# Sheet1_GMAX0505_2518_MB.net
KiCad netlist of a schematic drawn in Altium Designer
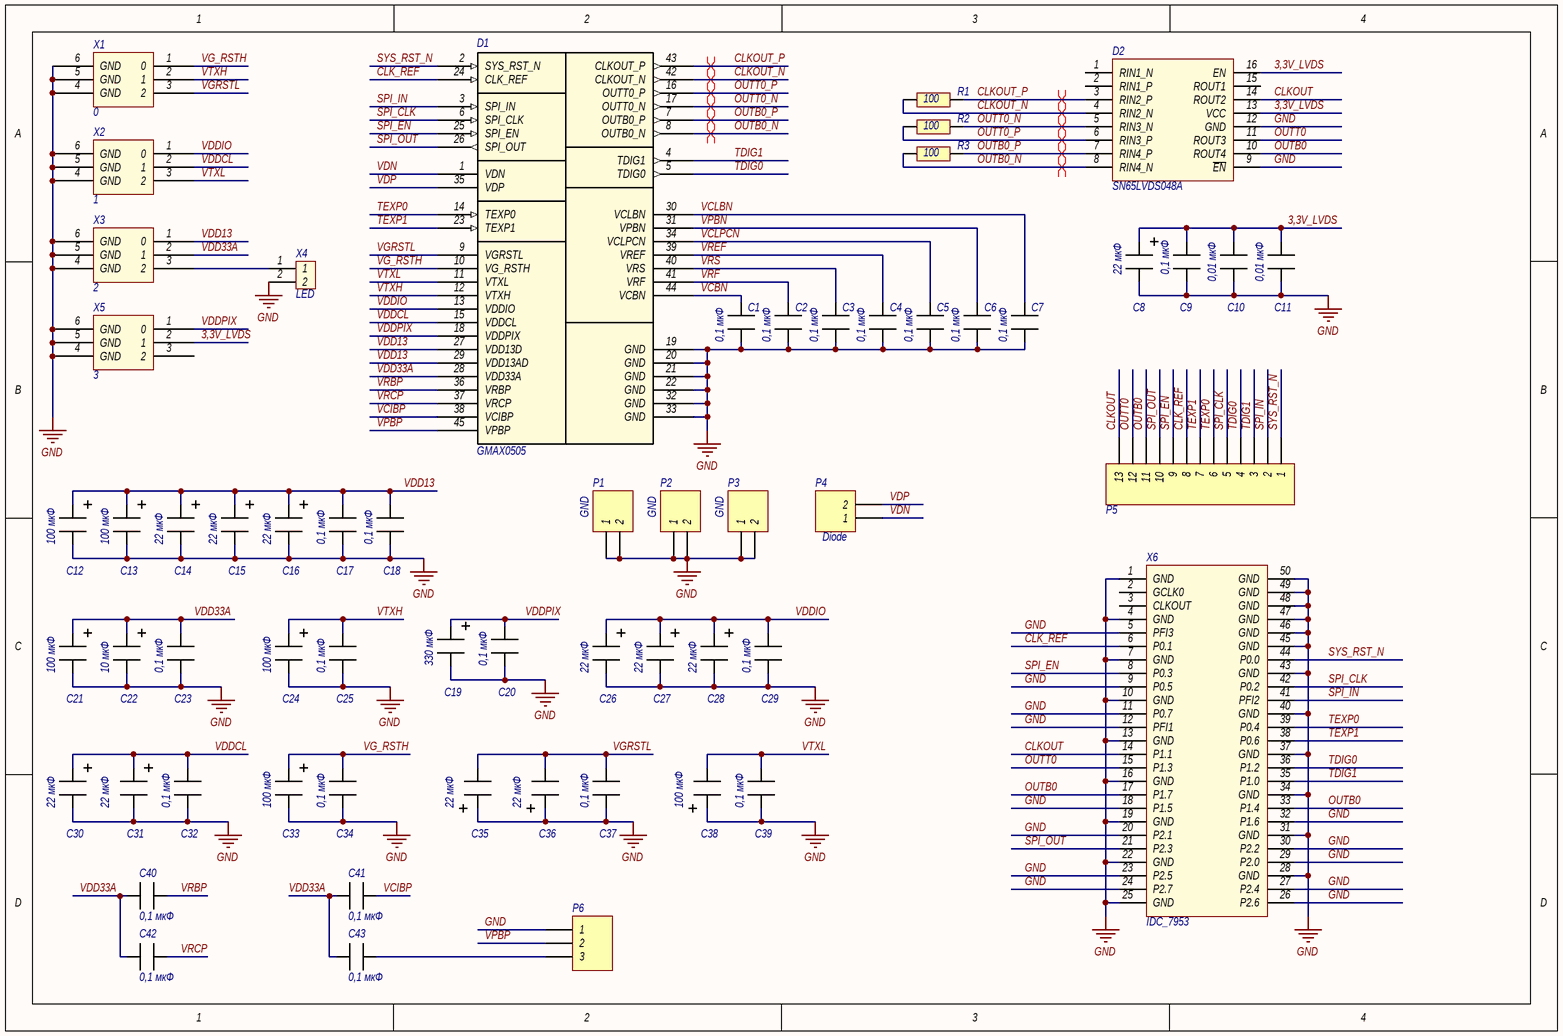
[diagram p0: Sheet1_GMAX0505_2518_MB.SchDoc]

(export (version "E")
  (design (tool "Eeschema 10.0.6"))
  (components
    (comp (ref "C1") (value "0,1 мкФ") (footprint "CAP_SMALL") (libsource (lib "Schlib") (part "CAP_SMALL")))
    (comp (ref "C2") (value "0,1 мкФ") (footprint "CAP_SMALL") (libsource (lib "Schlib") (part "CAP_SMALL")))
    (comp (ref "C3") (value "0,1 мкФ") (footprint "CAP_SMALL") (libsource (lib "Schlib") (part "CAP_SMALL")))
    (comp (ref "C4") (value "0,1 мкФ") (footprint "CAP_SMALL") (libsource (lib "Schlib") (part "CAP_SMALL")))
    (comp (ref "C5") (value "0,1 мкФ") (footprint "CAP_SMALL") (libsource (lib "Schlib") (part "CAP_SMALL")))
    (comp (ref "C6") (value "0,1 мкФ") (footprint "CAP_SMALL") (libsource (lib "Schlib") (part "CAP_SMALL")))
    (comp (ref "C7") (value "0,1 мкФ") (footprint "CAP_SMALL") (libsource (lib "Schlib") (part "CAP_SMALL")))
    (comp (ref "C8")
      (value "22 мкФ")
      (footprint "Cap_0511_electrolitic")
      (libsource (lib "Schlib") (part "Cap_electrolotoc_0511"))
    )
    (comp (ref "C9") (value "0,1 мкФ") (footprint "CAP_SMALL") (libsource (lib "Schlib") (part "CAP_SMALL")))
    (comp (ref "C10")
      (value "0,01 мкФ")
      (footprint "CAP_SMALL")
      (libsource (lib "Schlib") (part "CAP_SMALL"))
    )
    (comp (ref "C11")
      (value "0,01 мкФ")
      (footprint "CAP_SMALL")
      (libsource (lib "Schlib") (part "CAP_SMALL"))
    )
    (comp (ref "C12")
      (value "100 мкФ")
      (footprint "Cap_0612_electrolitic")
      (libsource (lib "Schlib") (part "Cap_electrolotoc_0612"))
    )
    (comp (ref "C13")
      (value "100 мкФ")
      (footprint "Cap_0612_electrolitic")
      (libsource (lib "Schlib") (part "Cap_electrolotoc_0612"))
    )
    (comp (ref "C14")
      (value "22 мкФ")
      (footprint "Cap_0511_electrolitic")
      (libsource (lib "Schlib") (part "Cap_electrolotoc_0511"))
    )
    (comp (ref "C15")
      (value "22 мкФ")
      (footprint "Cap_0511_electrolitic")
      (libsource (lib "Schlib") (part "Cap_electrolotoc_0511"))
    )
    (comp (ref "C16")
      (value "22 мкФ")
      (footprint "Cap_0511_electrolitic")
      (libsource (lib "Schlib") (part "Cap_electrolotoc_0511"))
    )
    (comp (ref "C17") (value "0,1 мкФ") (footprint "CAP_SMALL") (libsource (lib "Schlib") (part "CAP_SMALL")))
    (comp (ref "C18") (value "0,1 мкФ") (footprint "CAP_SMALL") (libsource (lib "Schlib") (part "CAP_SMALL")))
    (comp (ref "C19")
      (value "330 мкФ")
      (footprint "Cap_1013_electrolitic")
      (libsource (lib "Schlib") (part "Cap_electrolotoc_1013"))
    )
    (comp (ref "C20") (value "0,1 мкФ") (footprint "CAP_SMALL") (libsource (lib "Schlib") (part "CAP_SMALL")))
    (comp (ref "C21")
      (value "100 мкФ")
      (footprint "Cap_0612_electrolitic")
      (libsource (lib "Schlib") (part "Cap_electrolotoc_0612"))
    )
    (comp (ref "C22")
      (value "10 мкФ")
      (footprint "Cap_0511_electrolitic")
      (libsource (lib "Schlib") (part "Cap_electrolotoc_0511"))
    )
    (comp (ref "C23") (value "0,1 мкФ") (footprint "CAP_SMALL") (libsource (lib "Schlib") (part "CAP_SMALL")))
    (comp (ref "C24")
      (value "100 мкФ")
      (footprint "Cap_0612_electrolitic")
      (libsource (lib "Schlib") (part "Cap_electrolotoc_0612"))
    )
    (comp (ref "C25") (value "0,1 мкФ") (footprint "CAP_SMALL") (libsource (lib "Schlib") (part "CAP_SMALL")))
    (comp (ref "C26")
      (value "22 мкФ")
      (footprint "Cap_0511_electrolitic")
      (libsource (lib "Schlib") (part "Cap_electrolotoc_0511"))
    )
    (comp (ref "C27")
      (value "22 мкФ")
      (footprint "Cap_0511_electrolitic")
      (libsource (lib "Schlib") (part "Cap_electrolotoc_0511"))
    )
    (comp (ref "C28")
      (value "22 мкФ")
      (footprint "Cap_0511_electrolitic")
      (libsource (lib "Schlib") (part "Cap_electrolotoc_0511"))
    )
    (comp (ref "C29") (value "0,1 мкФ") (footprint "CAP_SMALL") (libsource (lib "Schlib") (part "CAP_SMALL")))
    (comp (ref "C30")
      (value "22 мкФ")
      (footprint "Cap_0511_electrolitic")
      (libsource (lib "Schlib") (part "Cap_electrolotoc_0511"))
    )
    (comp (ref "C31")
      (value "22 мкФ")
      (footprint "Cap_0511_electrolitic")
      (libsource (lib "Schlib") (part "Cap_electrolotoc_0511"))
    )
    (comp (ref "C32") (value "0,1 мкФ") (footprint "CAP_SMALL") (libsource (lib "Schlib") (part "CAP_SMALL")))
    (comp (ref "C33")
      (value "100 мкФ")
      (footprint "Cap_0612_electrolitic")
      (libsource (lib "Schlib") (part "Cap_electrolotoc_0612"))
    )
    (comp (ref "C34") (value "0,1 мкФ") (footprint "CAP_SMALL") (libsource (lib "Schlib") (part "CAP_SMALL")))
    (comp (ref "C35")
      (value "22 мкФ")
      (footprint "Cap_0511_electrolitic")
      (libsource (lib "Schlib") (part "Cap_electrolotoc_0511"))
    )
    (comp (ref "C36")
      (value "22 мкФ")
      (footprint "Cap_0511_electrolitic")
      (libsource (lib "Schlib") (part "Cap_electrolotoc_0511"))
    )
    (comp (ref "C37") (value "0,1 мкФ") (footprint "CAP_SMALL") (libsource (lib "Schlib") (part "CAP_SMALL")))
    (comp (ref "C38")
      (value "100 мкФ")
      (footprint "Cap_0612_electrolitic")
      (libsource (lib "Schlib") (part "Cap_electrolotoc_0612"))
    )
    (comp (ref "C39") (value "0,1 мкФ") (footprint "CAP_SMALL") (libsource (lib "Schlib") (part "CAP_SMALL")))
    (comp (ref "C40") (value "0,1 мкФ") (footprint "CAP_SMALL") (libsource (lib "Schlib") (part "CAP_SMALL")))
    (comp (ref "C41") (value "0,1 мкФ") (footprint "CAP_SMALL") (libsource (lib "Schlib") (part "CAP_SMALL")))
    (comp (ref "C42") (value "0,1 мкФ") (footprint "CAP_SMALL") (libsource (lib "Schlib") (part "CAP_SMALL")))
    (comp (ref "C43") (value "0,1 мкФ") (footprint "CAP_SMALL") (libsource (lib "Schlib") (part "CAP_SMALL")))
    (comp (ref "D1")
      (value "GMAX0505")
      (footprint "GMAX0505_MEZ")
      (libsource (lib "Schlib") (part "GMAX0505_MEZ"))
    )
    (comp (ref "D2")
      (value "SN65LVDS048A")
      (footprint "SN65LVDS048A (4LVDS)")
      (libsource (lib "Schlib") (part "SN65LVDS048A (4LVDS)"))
    )
    (comp (ref "P1")
      (value "GND")
      (footprint "HDR1X2")
      (description "Header, 2-Pin")
      (fields (field (name "PUBLISHER") "Altium Limited"))
      (libsource (lib "") (part "Header 2_1"))
    )
    (comp (ref "P2")
      (value "GND")
      (footprint "HDR1X2")
      (description "Header, 2-Pin")
      (fields (field (name "PUBLISHER") "Altium Limited"))
      (libsource (lib "") (part "Header 2_1"))
    )
    (comp (ref "P3")
      (value "GND")
      (footprint "HDR1X2")
      (description "Header, 2-Pin")
      (fields (field (name "PUBLISHER") "Altium Limited"))
      (libsource (lib "") (part "Header 2_1"))
    )
    (comp (ref "P4")
      (value "Diode")
      (footprint "HDR1X2")
      (description "Header, 2-Pin")
      (fields (field (name "PUBLISHER") "Altium Limited"))
      (libsource (lib "Miscellaneous Connectors") (part "Header 2"))
    )
    (comp (ref "P5")
      (value "Header 13")
      (footprint "HDR1X13")
      (description "Header, 13-Pin")
      (fields (field (name "PUBLISHER") "Altium Limited"))
      (libsource (lib "Miscellaneous Connectors") (part "Header 13"))
    )
    (comp (ref "P6")
      (value "VPBP")
      (footprint "HDR1X3")
      (description "Header, 3-Pin")
      (fields (field (name "PUBLISHER") "Altium Limited"))
      (libsource (lib "Miscellaneous Connectors") (part "Header 3"))
    )
    (comp (ref "R1") (value "100") (footprint "RES") (libsource (lib "Schlib") (part "RES")))
    (comp (ref "R2") (value "100") (footprint "RES") (libsource (lib "Schlib") (part "RES")))
    (comp (ref "R3") (value "100") (footprint "RES") (libsource (lib "Schlib") (part "RES")))
    (comp (ref "X1") (value "0") (footprint "POWER") (libsource (lib "Schlib") (part "POWER")))
    (comp (ref "X2") (value "1") (footprint "POWER") (libsource (lib "Schlib") (part "POWER")))
    (comp (ref "X3") (value "2") (footprint "POWER") (libsource (lib "Schlib") (part "POWER")))
    (comp (ref "X4") (value "LED") (footprint "KLEMMNIK_2") (libsource (lib "Schlib") (part "KLEMMNIK_2")))
    (comp (ref "X5") (value "3") (footprint "POWER") (libsource (lib "Schlib") (part "POWER")))
    (comp (ref "X6") (value "IDC_7953") (footprint "IDC_7953") (libsource (lib "VPL") (part "IDC_7953")))
  )
  (nets
    (net (code "1") (name "/3,3V_LVDS") (class "Default")
      (node (ref "C10") (pin "2") (pinfunction "2_2") (pintype "passive"))
      (node (ref "C11") (pin "2") (pinfunction "2_2") (pintype "passive"))
      (node (ref "C8") (pin "1") (pinfunction "1_1") (pintype "passive"))
      (node (ref "C9") (pin "2") (pinfunction "2_2") (pintype "passive"))
      (node (ref "D2") (pin "13") (pinfunction "VCC_13") (pintype "passive"))
      (node (ref "D2") (pin "16") (pinfunction "EN_16") (pintype "passive"))
      (node (ref "X5") (pin "2") (pinfunction "1_2") (pintype "passive"))
    )
    (net (code "2") (name "/CLKOUT") (class "Default")
      (node (ref "D2") (pin "14") (pinfunction "ROUT2_14") (pintype "passive"))
      (node (ref "P5") (pin "13") (pinfunction "13_13") (pintype "passive"))
      (node (ref "X6") (pin "14") (pinfunction "P1.1_14") (pintype "passive"))
    )
    (net (code "3") (name "/CLKOUT_N") (class "Default")
      (node (ref "D1") (pin "42") (pinfunction "CLKOUT_N_42") (pintype "output"))
      (node (ref "D2") (pin "4") (pinfunction "RIN2_N_4") (pintype "passive"))
      (node (ref "R1") (pin "2") (pinfunction "2_2") (pintype "passive"))
    )
    (net (code "4") (name "/CLKOUT_P") (class "Default")
      (node (ref "D1") (pin "43") (pinfunction "CLKOUT_P_43") (pintype "output"))
      (node (ref "D2") (pin "3") (pinfunction "RIN2_P_3") (pintype "passive"))
      (node (ref "R1") (pin "1") (pinfunction "1_1") (pintype "passive"))
    )
    (net (code "5") (name "/CLK_REF") (class "Default")
      (node (ref "D1") (pin "24") (pinfunction "CLK_REF_24") (pintype "input"))
      (node (ref "P5") (pin "8") (pinfunction "8_8") (pintype "passive"))
      (node (ref "X6") (pin "6") (pinfunction "P0.1_6") (pintype "passive"))
    )
    (net (code "6") (name "/OUTB0") (class "Default")
      (node (ref "D2") (pin "10") (pinfunction "ROUT4_10") (pintype "passive"))
      (node (ref "P5") (pin "11") (pinfunction "11_11") (pintype "passive"))
      (node (ref "X6") (pin "17") (pinfunction "P1.7_17") (pintype "passive"))
      (node (ref "X6") (pin "33") (pinfunction "P1.4_33") (pintype "passive"))
    )
    (net (code "7") (name "/OUTB0_N") (class "Default")
      (node (ref "D1") (pin "8") (pinfunction "OUTB0_N_8") (pintype "output"))
      (node (ref "D2") (pin "8") (pinfunction "RIN4_N_8") (pintype "passive"))
      (node (ref "R3") (pin "2") (pinfunction "2_2") (pintype "passive"))
    )
    (net (code "8") (name "/OUTB0_P") (class "Default")
      (node (ref "D1") (pin "7") (pinfunction "OUTB0_P_7") (pintype "output"))
      (node (ref "D2") (pin "7") (pinfunction "RIN4_P_7") (pintype "passive"))
      (node (ref "R3") (pin "1") (pinfunction "1_1") (pintype "passive"))
    )
    (net (code "9") (name "/OUTT0") (class "Default")
      (node (ref "D2") (pin "11") (pinfunction "ROUT3_11") (pintype "passive"))
      (node (ref "P5") (pin "12") (pinfunction "12_12") (pintype "passive"))
      (node (ref "X6") (pin "15") (pinfunction "P1.3_15") (pintype "passive"))
    )
    (net (code "10") (name "/OUTT0_N") (class "Default")
      (node (ref "D1") (pin "17") (pinfunction "OUTT0_N_17") (pintype "output"))
      (node (ref "D2") (pin "5") (pinfunction "RIN3_N_5") (pintype "passive"))
      (node (ref "R2") (pin "1") (pinfunction "1_1") (pintype "passive"))
    )
    (net (code "11") (name "/OUTT0_P") (class "Default")
      (node (ref "D1") (pin "16") (pinfunction "OUTT0_P_16") (pintype "output"))
      (node (ref "D2") (pin "6") (pinfunction "RIN3_P_6") (pintype "passive"))
      (node (ref "R2") (pin "2") (pinfunction "2_2") (pintype "passive"))
    )
    (net (code "12") (name "/SPI_CLK") (class "Default")
      (node (ref "D1") (pin "6") (pinfunction "SPI_CLK_6") (pintype "input"))
      (node (ref "P5") (pin "5") (pinfunction "5_5") (pintype "passive"))
      (node (ref "X6") (pin "42") (pinfunction "P0.2_42") (pintype "passive"))
    )
    (net (code "13") (name "/SPI_EN") (class "Default")
      (node (ref "D1") (pin "25") (pinfunction "SPI_EN_25") (pintype "input"))
      (node (ref "P5") (pin "9") (pinfunction "9_9") (pintype "passive"))
      (node (ref "X6") (pin "8") (pinfunction "P0.3_8") (pintype "passive"))
    )
    (net (code "14") (name "/SPI_IN") (class "Default")
      (node (ref "D1") (pin "3") (pinfunction "SPI_IN_3") (pintype "input"))
      (node (ref "P5") (pin "2") (pinfunction "2_2") (pintype "passive"))
      (node (ref "X6") (pin "41") (pinfunction "PFI2_41") (pintype "passive"))
    )
    (net (code "15") (name "/SPI_OUT") (class "Default")
      (node (ref "D1") (pin "26") (pinfunction "SPI_OUT_26") (pintype "output"))
      (node (ref "P5") (pin "10") (pinfunction "10_10") (pintype "passive"))
      (node (ref "X6") (pin "21") (pinfunction "P2.3_21") (pintype "passive"))
    )
    (net (code "16") (name "/SYS_RST_N") (class "Default")
      (node (ref "D1") (pin "2") (pinfunction "SYS_RST_N_2") (pintype "input"))
      (node (ref "P5") (pin "1") (pinfunction "1_1") (pintype "passive"))
      (node (ref "X6") (pin "44") (pinfunction "P0.0_44") (pintype "passive"))
    )
    (net (code "17") (name "/TDIG0") (class "Default")
      (node (ref "D1") (pin "5") (pinfunction "TDIG0_5") (pintype "output"))
      (node (ref "P5") (pin "4") (pinfunction "4_4") (pintype "passive"))
      (node (ref "X6") (pin "36") (pinfunction "P1.2_36") (pintype "passive"))
    )
    (net (code "18") (name "/TDIG1") (class "Default")
      (node (ref "D1") (pin "4") (pinfunction "TDIG1_4") (pintype "output"))
      (node (ref "P5") (pin "3") (pinfunction "3_3") (pintype "passive"))
      (node (ref "X6") (pin "35") (pinfunction "P1.0_35") (pintype "passive"))
    )
    (net (code "19") (name "/TEXP0") (class "Default")
      (node (ref "D1") (pin "14") (pinfunction "TEXP0_14") (pintype "input"))
      (node (ref "P5") (pin "6") (pinfunction "6_6") (pintype "passive"))
      (node (ref "X6") (pin "39") (pinfunction "P0.4_39") (pintype "passive"))
    )
    (net (code "20") (name "/TEXP1") (class "Default")
      (node (ref "D1") (pin "23") (pinfunction "TEXP1_23") (pintype "input"))
      (node (ref "P5") (pin "7") (pinfunction "7_7") (pintype "passive"))
      (node (ref "X6") (pin "38") (pinfunction "P0.6_38") (pintype "passive"))
    )
    (net (code "21") (name "/VCBN") (class "Default")
      (node (ref "C1") (pin "1") (pinfunction "1_1") (pintype "passive"))
      (node (ref "D1") (pin "44") (pinfunction "VCBN_44") (pintype "passive"))
    )
    (net (code "22") (name "/VCIBP") (class "Default")
      (node (ref "C41") (pin "1") (pinfunction "1_1") (pintype "passive"))
      (node (ref "D1") (pin "38") (pinfunction "VCIBP_38") (pintype "passive"))
    )
    (net (code "23") (name "/VCLBN") (class "Default")
      (node (ref "C7") (pin "1") (pinfunction "1_1") (pintype "passive"))
      (node (ref "D1") (pin "30") (pinfunction "VCLBN_30") (pintype "passive"))
    )
    (net (code "24") (name "/VCLPCN") (class "Default")
      (node (ref "C5") (pin "1") (pinfunction "1_1") (pintype "passive"))
      (node (ref "D1") (pin "34") (pinfunction "VCLPCN_34") (pintype "passive"))
    )
    (net (code "25") (name "/VDD13") (class "Default")
      (node (ref "C12") (pin "1") (pinfunction "1_1") (pintype "passive"))
      (node (ref "C13") (pin "1") (pinfunction "1_1") (pintype "passive"))
      (node (ref "C14") (pin "1") (pinfunction "1_1") (pintype "passive"))
      (node (ref "C15") (pin "1") (pinfunction "1_1") (pintype "passive"))
      (node (ref "C16") (pin "1") (pinfunction "1_1") (pintype "passive"))
      (node (ref "C17") (pin "1") (pinfunction "1_1") (pintype "passive"))
      (node (ref "C18") (pin "1") (pinfunction "1_1") (pintype "passive"))
      (node (ref "D1") (pin "27") (pinfunction "VDD13D_27") (pintype "passive"))
      (node (ref "D1") (pin "29") (pinfunction "VDD13AD_29") (pintype "passive"))
      (node (ref "X3") (pin "1") (pinfunction "0_1") (pintype "passive"))
    )
    (net (code "26") (name "/VDD33A") (class "Default")
      (node (ref "C21") (pin "1") (pinfunction "1_1") (pintype "passive"))
      (node (ref "C22") (pin "1") (pinfunction "1_1") (pintype "passive"))
      (node (ref "C23") (pin "1") (pinfunction "1_1") (pintype "passive"))
      (node (ref "C40") (pin "2") (pinfunction "2_2") (pintype "passive"))
      (node (ref "C41") (pin "2") (pinfunction "2_2") (pintype "passive"))
      (node (ref "C42") (pin "2") (pinfunction "2_2") (pintype "passive"))
      (node (ref "C43") (pin "2") (pinfunction "2_2") (pintype "passive"))
      (node (ref "D1") (pin "28") (pinfunction "VDD33A_28") (pintype "passive"))
      (node (ref "X3") (pin "2") (pinfunction "1_2") (pintype "passive"))
    )
    (net (code "27") (name "/VDDCL") (class "Default")
      (node (ref "C30") (pin "1") (pinfunction "1_1") (pintype "passive"))
      (node (ref "C31") (pin "1") (pinfunction "1_1") (pintype "passive"))
      (node (ref "C32") (pin "2") (pinfunction "2_2") (pintype "passive"))
      (node (ref "D1") (pin "15") (pinfunction "VDDCL_15") (pintype "passive"))
      (node (ref "X2") (pin "2") (pinfunction "1_2") (pintype "passive"))
    )
    (net (code "28") (name "/VDDIO") (class "Default")
      (node (ref "C26") (pin "1") (pinfunction "1_1") (pintype "passive"))
      (node (ref "C27") (pin "1") (pinfunction "1_1") (pintype "passive"))
      (node (ref "C28") (pin "1") (pinfunction "1_1") (pintype "passive"))
      (node (ref "C29") (pin "1") (pinfunction "1_1") (pintype "passive"))
      (node (ref "D1") (pin "13") (pinfunction "VDDIO_13") (pintype "passive"))
      (node (ref "X2") (pin "1") (pinfunction "0_1") (pintype "passive"))
    )
    (net (code "29") (name "/VDDPIX") (class "Default")
      (node (ref "C19") (pin "1") (pinfunction "1_1") (pintype "passive"))
      (node (ref "C20") (pin "1") (pinfunction "1_1") (pintype "passive"))
      (node (ref "D1") (pin "18") (pinfunction "VDDPIX_18") (pintype "passive"))
      (node (ref "X5") (pin "1") (pinfunction "0_1") (pintype "passive"))
    )
    (net (code "30") (name "/VDN") (class "Default")
      (node (ref "D1") (pin "1") (pinfunction "VDN_1") (pintype "passive"))
      (node (ref "P4") (pin "1") (pinfunction "1_1") (pintype "passive"))
    )
    (net (code "31") (name "/VDP") (class "Default")
      (node (ref "D1") (pin "35") (pinfunction "VDP_35") (pintype "passive"))
      (node (ref "P4") (pin "2") (pinfunction "2_2") (pintype "passive"))
    )
    (net (code "32") (name "/VGRSTL") (class "Default")
      (node (ref "C35") (pin "2") (pinfunction "2_2") (pintype "passive"))
      (node (ref "C36") (pin "2") (pinfunction "2_2") (pintype "passive"))
      (node (ref "C37") (pin "2") (pinfunction "2_2") (pintype "passive"))
      (node (ref "D1") (pin "9") (pinfunction "VGRSTL_9") (pintype "passive"))
      (node (ref "X1") (pin "3") (pinfunction "2_3") (pintype "passive"))
    )
    (net (code "33") (name "/VG_RSTH") (class "Default")
      (node (ref "C33") (pin "1") (pinfunction "1_1") (pintype "passive"))
      (node (ref "C34") (pin "1") (pinfunction "1_1") (pintype "passive"))
      (node (ref "D1") (pin "10") (pinfunction "VG_RSTH_10") (pintype "passive"))
      (node (ref "X1") (pin "1") (pinfunction "0_1") (pintype "passive"))
    )
    (net (code "34") (name "/VPBN") (class "Default")
      (node (ref "C6") (pin "1") (pinfunction "1_1") (pintype "passive"))
      (node (ref "D1") (pin "31") (pinfunction "VPBN_31") (pintype "passive"))
    )
    (net (code "35") (name "/VPBP") (class "Default")
      (node (ref "D1") (pin "45") (pinfunction "VPBP_45") (pintype "passive"))
      (node (ref "P6") (pin "2") (pinfunction "2_2") (pintype "passive"))
    )
    (net (code "36") (name "/VRBP") (class "Default")
      (node (ref "C40") (pin "1") (pinfunction "1_1") (pintype "passive"))
      (node (ref "D1") (pin "36") (pinfunction "VRBP_36") (pintype "passive"))
    )
    (net (code "37") (name "/VRCP") (class "Default")
      (node (ref "C42") (pin "1") (pinfunction "1_1") (pintype "passive"))
      (node (ref "D1") (pin "37") (pinfunction "VRCP_37") (pintype "passive"))
    )
    (net (code "38") (name "/VREF") (class "Default")
      (node (ref "C4") (pin "1") (pinfunction "1_1") (pintype "passive"))
      (node (ref "D1") (pin "39") (pinfunction "VREF_39") (pintype "passive"))
    )
    (net (code "39") (name "/VRF") (class "Default")
      (node (ref "C2") (pin "1") (pinfunction "1_1") (pintype "passive"))
      (node (ref "D1") (pin "41") (pinfunction "VRF_41") (pintype "passive"))
    )
    (net (code "40") (name "/VRS") (class "Default")
      (node (ref "C3") (pin "1") (pinfunction "1_1") (pintype "passive"))
      (node (ref "D1") (pin "40") (pinfunction "VRS_40") (pintype "passive"))
    )
    (net (code "41") (name "/VTXH") (class "Default")
      (node (ref "C24") (pin "1") (pinfunction "1_1") (pintype "passive"))
      (node (ref "C25") (pin "1") (pinfunction "1_1") (pintype "passive"))
      (node (ref "D1") (pin "12") (pinfunction "VTXH_12") (pintype "passive"))
      (node (ref "X1") (pin "2") (pinfunction "1_2") (pintype "passive"))
    )
    (net (code "42") (name "/VTXL") (class "Default")
      (node (ref "C38") (pin "2") (pinfunction "2_2") (pintype "passive"))
      (node (ref "C39") (pin "1") (pinfunction "1_1") (pintype "passive"))
      (node (ref "D1") (pin "11") (pinfunction "VTXL_11") (pintype "passive"))
      (node (ref "X2") (pin "3") (pinfunction "2_3") (pintype "passive"))
    )
    (net (code "43") (name "GND") (class "Default")
      (node (ref "C1") (pin "2") (pinfunction "2_2") (pintype "passive"))
      (node (ref "C10") (pin "1") (pinfunction "1_1") (pintype "passive"))
      (node (ref "C11") (pin "1") (pinfunction "1_1") (pintype "passive"))
      (node (ref "C12") (pin "2") (pinfunction "2_2") (pintype "passive"))
      (node (ref "C13") (pin "2") (pinfunction "2_2") (pintype "passive"))
      (node (ref "C14") (pin "2") (pinfunction "2_2") (pintype "passive"))
      (node (ref "C15") (pin "2") (pinfunction "2_2") (pintype "passive"))
      (node (ref "C16") (pin "2") (pinfunction "2_2") (pintype "passive"))
      (node (ref "C17") (pin "2") (pinfunction "2_2") (pintype "passive"))
      (node (ref "C18") (pin "2") (pinfunction "2_2") (pintype "passive"))
      (node (ref "C19") (pin "2") (pinfunction "2_2") (pintype "passive"))
      (node (ref "C2") (pin "2") (pinfunction "2_2") (pintype "passive"))
      (node (ref "C20") (pin "2") (pinfunction "2_2") (pintype "passive"))
      (node (ref "C21") (pin "2") (pinfunction "2_2") (pintype "passive"))
      (node (ref "C22") (pin "2") (pinfunction "2_2") (pintype "passive"))
      (node (ref "C23") (pin "2") (pinfunction "2_2") (pintype "passive"))
      (node (ref "C24") (pin "2") (pinfunction "2_2") (pintype "passive"))
      (node (ref "C25") (pin "2") (pinfunction "2_2") (pintype "passive"))
      (node (ref "C26") (pin "2") (pinfunction "2_2") (pintype "passive"))
      (node (ref "C27") (pin "2") (pinfunction "2_2") (pintype "passive"))
      (node (ref "C28") (pin "2") (pinfunction "2_2") (pintype "passive"))
      (node (ref "C29") (pin "2") (pinfunction "2_2") (pintype "passive"))
      (node (ref "C3") (pin "2") (pinfunction "2_2") (pintype "passive"))
      (node (ref "C30") (pin "2") (pinfunction "2_2") (pintype "passive"))
      (node (ref "C31") (pin "2") (pinfunction "2_2") (pintype "passive"))
      (node (ref "C32") (pin "1") (pinfunction "1_1") (pintype "passive"))
      (node (ref "C33") (pin "2") (pinfunction "2_2") (pintype "passive"))
      (node (ref "C34") (pin "2") (pinfunction "2_2") (pintype "passive"))
      (node (ref "C35") (pin "1") (pinfunction "1_1") (pintype "passive"))
      (node (ref "C36") (pin "1") (pinfunction "1_1") (pintype "passive"))
      (node (ref "C37") (pin "1") (pinfunction "1_1") (pintype "passive"))
      (node (ref "C38") (pin "1") (pinfunction "1_1") (pintype "passive"))
      (node (ref "C39") (pin "2") (pinfunction "2_2") (pintype "passive"))
      (node (ref "C4") (pin "2") (pinfunction "2_2") (pintype "passive"))
      (node (ref "C5") (pin "2") (pinfunction "2_2") (pintype "passive"))
      (node (ref "C6") (pin "2") (pinfunction "2_2") (pintype "passive"))
      (node (ref "C7") (pin "2") (pinfunction "2_2") (pintype "passive"))
      (node (ref "C8") (pin "2") (pinfunction "2_2") (pintype "passive"))
      (node (ref "C9") (pin "1") (pinfunction "1_1") (pintype "passive"))
      (node (ref "D1") (pin "19") (pinfunction "GND_19") (pintype "passive"))
      (node (ref "D1") (pin "20") (pinfunction "GND_20") (pintype "passive"))
      (node (ref "D1") (pin "21") (pinfunction "GND_21") (pintype "passive"))
      (node (ref "D1") (pin "22") (pinfunction "GND_22") (pintype "passive"))
      (node (ref "D1") (pin "32") (pinfunction "GND_32") (pintype "passive"))
      (node (ref "D1") (pin "33") (pinfunction "GND_33") (pintype "passive"))
      (node (ref "D2") (pin "12") (pinfunction "GND_12") (pintype "passive"))
      (node (ref "D2") (pin "9") (pinfunction "~{EN}_9") (pintype "passive"))
      (node (ref "P1") (pin "1") (pinfunction "1_1") (pintype "passive"))
      (node (ref "P1") (pin "2") (pinfunction "2_2") (pintype "passive"))
      (node (ref "P2") (pin "1") (pinfunction "1_1") (pintype "passive"))
      (node (ref "P2") (pin "2") (pinfunction "2_2") (pintype "passive"))
      (node (ref "P3") (pin "1") (pinfunction "1_1") (pintype "passive"))
      (node (ref "P3") (pin "2") (pinfunction "2_2") (pintype "passive"))
      (node (ref "P6") (pin "1") (pinfunction "1_1") (pintype "passive"))
      (node (ref "X1") (pin "4") (pinfunction "GND_4") (pintype "passive"))
      (node (ref "X1") (pin "5") (pinfunction "GND_5") (pintype "passive"))
      (node (ref "X1") (pin "6") (pinfunction "GND_6") (pintype "passive"))
      (node (ref "X2") (pin "4") (pinfunction "GND_4") (pintype "passive"))
      (node (ref "X2") (pin "5") (pinfunction "GND_5") (pintype "passive"))
      (node (ref "X2") (pin "6") (pinfunction "GND_6") (pintype "passive"))
      (node (ref "X3") (pin "4") (pinfunction "GND_4") (pintype "passive"))
      (node (ref "X3") (pin "5") (pinfunction "GND_5") (pintype "passive"))
      (node (ref "X3") (pin "6") (pinfunction "GND_6") (pintype "passive"))
      (node (ref "X4") (pin "2") (pinfunction "2_2") (pintype "passive"))
      (node (ref "X5") (pin "4") (pinfunction "GND_4") (pintype "passive"))
      (node (ref "X5") (pin "5") (pinfunction "GND_5") (pintype "passive"))
      (node (ref "X5") (pin "6") (pinfunction "GND_6") (pintype "passive"))
      (node (ref "X6") (pin "1") (pinfunction "GND_1") (pintype "passive"))
      (node (ref "X6") (pin "10") (pinfunction "GND_10") (pintype "passive"))
      (node (ref "X6") (pin "11") (pinfunction "P0.7_11") (pintype "passive"))
      (node (ref "X6") (pin "12") (pinfunction "PFI1_12") (pintype "passive"))
      (node (ref "X6") (pin "13") (pinfunction "GND_13") (pintype "passive"))
      (node (ref "X6") (pin "16") (pinfunction "GND_16") (pintype "passive"))
      (node (ref "X6") (pin "18") (pinfunction "P1.5_18") (pintype "passive"))
      (node (ref "X6") (pin "19") (pinfunction "GND_19") (pintype "passive"))
      (node (ref "X6") (pin "20") (pinfunction "P2.1_20") (pintype "passive"))
      (node (ref "X6") (pin "22") (pinfunction "GND_22") (pintype "passive"))
      (node (ref "X6") (pin "23") (pinfunction "P2.5_23") (pintype "passive"))
      (node (ref "X6") (pin "24") (pinfunction "P2.7_24") (pintype "passive"))
      (node (ref "X6") (pin "25") (pinfunction "GND_25") (pintype "passive"))
      (node (ref "X6") (pin "26") (pinfunction "P2.6_26") (pintype "passive"))
      (node (ref "X6") (pin "27") (pinfunction "P2.4_27") (pintype "passive"))
      (node (ref "X6") (pin "28") (pinfunction "GND_28") (pintype "passive"))
      (node (ref "X6") (pin "29") (pinfunction "P2.0_29") (pintype "passive"))
      (node (ref "X6") (pin "30") (pinfunction "P2.2_30") (pintype "passive"))
      (node (ref "X6") (pin "31") (pinfunction "GND_31") (pintype "passive"))
      (node (ref "X6") (pin "32") (pinfunction "P1.6_32") (pintype "passive"))
      (node (ref "X6") (pin "34") (pinfunction "GND_34") (pintype "passive"))
      (node (ref "X6") (pin "37") (pinfunction "GND_37") (pintype "passive"))
      (node (ref "X6") (pin "4") (pinfunction "GND_4") (pintype "passive"))
      (node (ref "X6") (pin "40") (pinfunction "GND_40") (pintype "passive"))
      (node (ref "X6") (pin "43") (pinfunction "GND_43") (pintype "passive"))
      (node (ref "X6") (pin "45") (pinfunction "GND_45") (pintype "passive"))
      (node (ref "X6") (pin "46") (pinfunction "GND_46") (pintype "passive"))
      (node (ref "X6") (pin "47") (pinfunction "GND_47") (pintype "passive"))
      (node (ref "X6") (pin "48") (pinfunction "GND_48") (pintype "passive"))
      (node (ref "X6") (pin "49") (pinfunction "GND_49") (pintype "passive"))
      (node (ref "X6") (pin "5") (pinfunction "PFI3_5") (pintype "passive"))
      (node (ref "X6") (pin "50") (pinfunction "GND_50") (pintype "passive"))
      (node (ref "X6") (pin "7") (pinfunction "GND_7") (pintype "passive"))
      (node (ref "X6") (pin "9") (pinfunction "P0.5_9") (pintype "passive"))
    )
    (net (code "44") (name "Net-(C43-Pad1)") (class "Default")
      (node (ref "C43") (pin "1") (pinfunction "1_1") (pintype "passive"))
      (node (ref "P6") (pin "3") (pinfunction "3_3") (pintype "passive"))
    )
    (net (code "45") (name "Net-(X3-2)") (class "Default")
      (node (ref "X3") (pin "3") (pinfunction "2_3") (pintype "passive"))
      (node (ref "X4") (pin "1") (pinfunction "1_1") (pintype "passive"))
    )
    (net (code "46") (name "unconnected-(D2-RIN1_N-Pad1)") (class "Default")
      (node (ref "D2") (pin "1") (pinfunction "RIN1_N_1") (pintype "passive"))
    )
    (net (code "47") (name "unconnected-(D2-RIN1_P-Pad2)") (class "Default")
      (node (ref "D2") (pin "2") (pinfunction "RIN1_P_2") (pintype "passive"))
    )
    (net (code "48") (name "unconnected-(D2-ROUT1-Pad15)") (class "Default")
      (node (ref "D2") (pin "15") (pinfunction "ROUT1_15") (pintype "passive"))
    )
    (net (code "49") (name "unconnected-(X5-2-Pad3)") (class "Default")
      (node (ref "X5") (pin "3") (pinfunction "2_3") (pintype "passive"))
    )
    (net (code "50") (name "unconnected-(X6-CLKOUT-Pad3)") (class "Default")
      (node (ref "X6") (pin "3") (pinfunction "CLKOUT_3") (pintype "passive"))
    )
    (net (code "51") (name "unconnected-(X6-GCLK0-Pad2)") (class "Default")
      (node (ref "X6") (pin "2") (pinfunction "GCLK0_2") (pintype "passive"))
    )
  )
)
